# NVME.net
KiCad netlist of a schematic drawn in Altium Designer
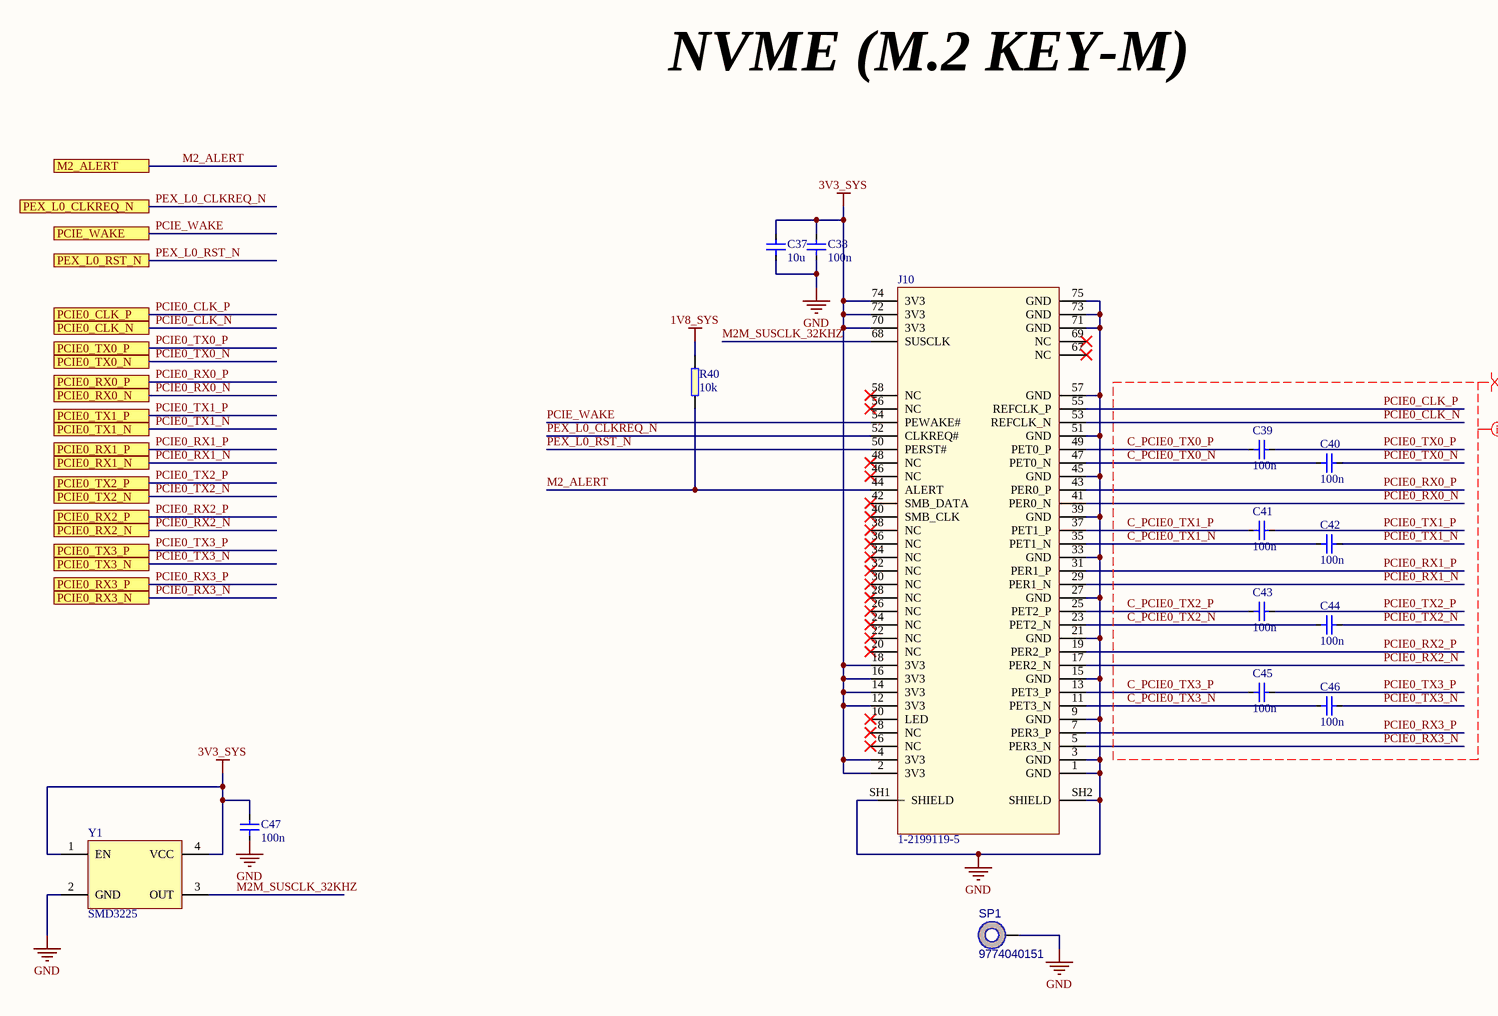
[diagram p0: NVME.SchDoc]

(export (version "E")
  (design (tool "Eeschema 10.0.6"))
  (components
    (comp (ref "C37")
      (value "10u")
      (footprint "C0402")
      (description "MLCC SMT Capacitor 10uF 0402")
      (fields (field (name "PARTNUMBER") "C_10u_0402") (field (name "MANUFACTURER") "TDK"))
      (libsource (lib "jetson-nano-baseboard") (part "C_10u_0402"))
    )
    (comp (ref "C38")
      (value "100n")
      (footprint "C0402")
      (description "MLCC SMT Capacitor 100n 0402")
      (fields (field (name "PARTNUMBER") "C_100n_0402") (field (name "MANUFACTURER") "TDK"))
      (libsource (lib "jetson-nano-baseboard") (part "C_100n_0402"))
    )
    (comp (ref "C39")
      (value "100n")
      (footprint "C0402")
      (description "MLCC SMT Capacitor 100n 0402")
      (fields (field (name "PARTNUMBER") "C_100n_0402") (field (name "MANUFACTURER") "TDK"))
      (libsource (lib "jetson-nano-baseboard") (part "C_100n_0402"))
    )
    (comp (ref "C40")
      (value "100n")
      (footprint "C0402")
      (description "MLCC SMT Capacitor 100n 0402")
      (fields (field (name "PARTNUMBER") "C_100n_0402") (field (name "MANUFACTURER") "TDK"))
      (libsource (lib "jetson-nano-baseboard") (part "C_100n_0402"))
    )
    (comp (ref "C41")
      (value "100n")
      (footprint "C0402")
      (description "MLCC SMT Capacitor 100n 0402")
      (fields (field (name "PARTNUMBER") "C_100n_0402") (field (name "MANUFACTURER") "TDK"))
      (libsource (lib "jetson-nano-baseboard") (part "C_100n_0402"))
    )
    (comp (ref "C42")
      (value "100n")
      (footprint "C0402")
      (description "MLCC SMT Capacitor 100n 0402")
      (fields (field (name "PARTNUMBER") "C_100n_0402") (field (name "MANUFACTURER") "TDK"))
      (libsource (lib "jetson-nano-baseboard") (part "C_100n_0402"))
    )
    (comp (ref "C43")
      (value "100n")
      (footprint "C0402")
      (description "MLCC SMT Capacitor 100n 0402")
      (fields (field (name "PARTNUMBER") "C_100n_0402") (field (name "MANUFACTURER") "TDK"))
      (libsource (lib "jetson-nano-baseboard") (part "C_100n_0402"))
    )
    (comp (ref "C44")
      (value "100n")
      (footprint "C0402")
      (description "MLCC SMT Capacitor 100n 0402")
      (fields (field (name "PARTNUMBER") "C_100n_0402") (field (name "MANUFACTURER") "TDK"))
      (libsource (lib "jetson-nano-baseboard") (part "C_100n_0402"))
    )
    (comp (ref "C45")
      (value "100n")
      (footprint "C0402")
      (description "MLCC SMT Capacitor 100n 0402")
      (fields (field (name "PARTNUMBER") "C_100n_0402") (field (name "MANUFACTURER") "TDK"))
      (libsource (lib "jetson-nano-baseboard") (part "C_100n_0402"))
    )
    (comp (ref "C46")
      (value "100n")
      (footprint "C0402")
      (description "MLCC SMT Capacitor 100n 0402")
      (fields (field (name "PARTNUMBER") "C_100n_0402") (field (name "MANUFACTURER") "TDK"))
      (libsource (lib "jetson-nano-baseboard") (part "C_100n_0402"))
    )
    (comp (ref "C47")
      (value "100n")
      (footprint "C0402")
      (description "MLCC SMT Capacitor 100n 0402")
      (fields (field (name "PARTNUMBER") "C_100n_0402") (field (name "MANUFACTURER") "TDK"))
      (libsource (lib "jetson-nano-baseboard") (part "C_100n_0402"))
    )
    (comp (ref "J10")
      (value "1-2199119-5")
      (footprint "1-2199119-5")
      (description "CONN FEMALE 67POS 0.020 GOLD")
      (fields (field (name "MANUFACTURER") "TE"))
      (libsource (lib "jetson-nano-baseboard") (part "1-2199119-5"))
    )
    (comp (ref "R40")
      (value "10k")
      (footprint "R0402")
      (description "RES, 10k, 0402")
      (fields (field (name "PARTNUMBER") "R_10k_0402") (field (name "MANUFACTURER") "MULTICOMP"))
      (libsource (lib "jetson-nano-baseboard") (part "R_10k_0402"))
    )
    (comp (ref "SP1")
      (value "9774040151")
      (footprint "MEC_STANDOFF_PTH_620C380P")
      (description "RND STANDOFF M2.5X0.45 STEEL 4MM")
      (fields (field (name "MANUFACTURER") "WURTH ELEKTRONIK"))
      (libsource (lib "jetson-nano-baseboard") (part "9774040151"))
    )
    (comp (ref "Y1")
      (value "SMD3225")
      (footprint "XTAL_SMD_4_032X025_D")
      (libsource (lib "jetson-nano-baseboard") (part "SMD3225"))
    )
  )
  (nets
    (net (code "1") (name "/C_PCIE0_TX0_N") (class "Default")
      (node (ref "C40") (pin "1") (pinfunction "1_1") (pintype "passive"))
      (node (ref "J10") (pin "47") (pinfunction "PET0_N_47") (pintype "passive"))
    )
    (net (code "2") (name "/C_PCIE0_TX0_P") (class "Default")
      (node (ref "C39") (pin "1") (pinfunction "1_1") (pintype "passive"))
      (node (ref "J10") (pin "49") (pinfunction "PET0_P_49") (pintype "passive"))
    )
    (net (code "3") (name "/C_PCIE0_TX1_N") (class "Default")
      (node (ref "C42") (pin "1") (pinfunction "1_1") (pintype "passive"))
      (node (ref "J10") (pin "35") (pinfunction "PET1_N_35") (pintype "passive"))
    )
    (net (code "4") (name "/C_PCIE0_TX1_P") (class "Default")
      (node (ref "C41") (pin "1") (pinfunction "1_1") (pintype "passive"))
      (node (ref "J10") (pin "37") (pinfunction "PET1_P_37") (pintype "passive"))
    )
    (net (code "5") (name "/C_PCIE0_TX2_N") (class "Default")
      (node (ref "C44") (pin "1") (pinfunction "1_1") (pintype "passive"))
      (node (ref "J10") (pin "23") (pinfunction "PET2_N_23") (pintype "passive"))
    )
    (net (code "6") (name "/C_PCIE0_TX2_P") (class "Default")
      (node (ref "C43") (pin "1") (pinfunction "1_1") (pintype "passive"))
      (node (ref "J10") (pin "25") (pinfunction "PET2_P_25") (pintype "passive"))
    )
    (net (code "7") (name "/C_PCIE0_TX3_N") (class "Default")
      (node (ref "C46") (pin "1") (pinfunction "1_1") (pintype "passive"))
      (node (ref "J10") (pin "11") (pinfunction "PET3_N_11") (pintype "passive"))
    )
    (net (code "8") (name "/C_PCIE0_TX3_P") (class "Default")
      (node (ref "C45") (pin "1") (pinfunction "1_1") (pintype "passive"))
      (node (ref "J10") (pin "13") (pinfunction "PET3_P_13") (pintype "passive"))
    )
    (net (code "9") (name "/M2M_SUSCLK_32KHZ") (class "Default")
      (node (ref "J10") (pin "68") (pinfunction "SUSCLK_68") (pintype "passive"))
      (node (ref "Y1") (pin "3") (pinfunction "OUT_3") (pintype "passive"))
    )
    (net (code "10") (name "/M2_ALERT") (class "Default")
      (node (ref "J10") (pin "44") (pinfunction "ALERT_44") (pintype "passive"))
      (node (ref "R40") (pin "1") (pintype "passive"))
    )
    (net (code "11") (name "/PCIE0_CLK_N") (class "Default")
      (node (ref "J10") (pin "53") (pinfunction "REFCLK_N_53") (pintype "passive"))
    )
    (net (code "12") (name "/PCIE0_CLK_P") (class "Default")
      (node (ref "J10") (pin "55") (pinfunction "REFCLK_P_55") (pintype "passive"))
    )
    (net (code "13") (name "/PCIE0_RX0_N") (class "Default")
      (node (ref "J10") (pin "41") (pinfunction "PER0_N_41") (pintype "passive"))
    )
    (net (code "14") (name "/PCIE0_RX0_P") (class "Default")
      (node (ref "J10") (pin "43") (pinfunction "PER0_P_43") (pintype "passive"))
    )
    (net (code "15") (name "/PCIE0_RX1_N") (class "Default")
      (node (ref "J10") (pin "29") (pinfunction "PER1_N_29") (pintype "passive"))
    )
    (net (code "16") (name "/PCIE0_RX1_P") (class "Default")
      (node (ref "J10") (pin "31") (pinfunction "PER1_P_31") (pintype "passive"))
    )
    (net (code "17") (name "/PCIE0_RX2_N") (class "Default")
      (node (ref "J10") (pin "17") (pinfunction "PER2_N_17") (pintype "passive"))
    )
    (net (code "18") (name "/PCIE0_RX2_P") (class "Default")
      (node (ref "J10") (pin "19") (pinfunction "PER2_P_19") (pintype "passive"))
    )
    (net (code "19") (name "/PCIE0_RX3_N") (class "Default")
      (node (ref "J10") (pin "5") (pinfunction "PER3_N_5") (pintype "passive"))
    )
    (net (code "20") (name "/PCIE0_RX3_P") (class "Default")
      (node (ref "J10") (pin "7") (pinfunction "PER3_P_7") (pintype "passive"))
    )
    (net (code "21") (name "/PCIE0_TX0_N") (class "Default")
      (node (ref "C40") (pin "2") (pinfunction "2_2") (pintype "passive"))
    )
    (net (code "22") (name "/PCIE0_TX0_P") (class "Default")
      (node (ref "C39") (pin "2") (pinfunction "2_2") (pintype "passive"))
    )
    (net (code "23") (name "/PCIE0_TX1_N") (class "Default")
      (node (ref "C42") (pin "2") (pinfunction "2_2") (pintype "passive"))
    )
    (net (code "24") (name "/PCIE0_TX1_P") (class "Default")
      (node (ref "C41") (pin "2") (pinfunction "2_2") (pintype "passive"))
    )
    (net (code "25") (name "/PCIE0_TX2_N") (class "Default")
      (node (ref "C44") (pin "2") (pinfunction "2_2") (pintype "passive"))
    )
    (net (code "26") (name "/PCIE0_TX2_P") (class "Default")
      (node (ref "C43") (pin "2") (pinfunction "2_2") (pintype "passive"))
    )
    (net (code "27") (name "/PCIE0_TX3_N") (class "Default")
      (node (ref "C46") (pin "2") (pinfunction "2_2") (pintype "passive"))
    )
    (net (code "28") (name "/PCIE0_TX3_P") (class "Default")
      (node (ref "C45") (pin "2") (pinfunction "2_2") (pintype "passive"))
    )
    (net (code "29") (name "/PCIE_WAKE") (class "Default")
      (node (ref "J10") (pin "54") (pinfunction "PEWAKE#_54") (pintype "passive"))
    )
    (net (code "30") (name "/PEX_L0_CLKREQ_N") (class "Default")
      (node (ref "J10") (pin "52") (pinfunction "CLKREQ#_52") (pintype "passive"))
    )
    (net (code "31") (name "/PEX_L0_RST_N") (class "Default")
      (node (ref "J10") (pin "50") (pinfunction "PERST#_50") (pintype "passive"))
    )
    (net (code "32") (name "1V8_SYS") (class "Default") (node (ref "R40") (pin "2") (pintype "passive")))
    (net (code "33") (name "3V3_SYS") (class "Default")
      (node (ref "C37") (pin "2") (pinfunction "2_2") (pintype "passive"))
      (node (ref "C38") (pin "2") (pinfunction "2_2") (pintype "passive"))
      (node (ref "C47") (pin "2") (pinfunction "2_2") (pintype "passive"))
      (node (ref "J10") (pin "12") (pinfunction "3V3_12") (pintype "passive"))
      (node (ref "J10") (pin "14") (pinfunction "3V3_14") (pintype "passive"))
      (node (ref "J10") (pin "16") (pinfunction "3V3_16") (pintype "passive"))
      (node (ref "J10") (pin "18") (pinfunction "3V3_18") (pintype "passive"))
      (node (ref "J10") (pin "2") (pinfunction "3V3_2") (pintype "passive"))
      (node (ref "J10") (pin "4") (pinfunction "3V3_4") (pintype "passive"))
      (node (ref "J10") (pin "70") (pinfunction "3V3_70") (pintype "passive"))
      (node (ref "J10") (pin "72") (pinfunction "3V3_72") (pintype "passive"))
      (node (ref "J10") (pin "74") (pinfunction "3V3_74") (pintype "passive"))
      (node (ref "Y1") (pin "1") (pinfunction "EN_1") (pintype "passive"))
      (node (ref "Y1") (pin "4") (pinfunction "VCC_4") (pintype "passive"))
    )
    (net (code "34") (name "GND") (class "Default")
      (node (ref "C37") (pin "1") (pinfunction "1_1") (pintype "passive"))
      (node (ref "C38") (pin "1") (pinfunction "1_1") (pintype "passive"))
      (node (ref "C47") (pin "1") (pinfunction "1_1") (pintype "passive"))
      (node (ref "J10") (pin "1") (pinfunction "GND_1") (pintype "passive"))
      (node (ref "J10") (pin "15") (pinfunction "GND_15") (pintype "passive"))
      (node (ref "J10") (pin "21") (pinfunction "GND_21") (pintype "passive"))
      (node (ref "J10") (pin "27") (pinfunction "GND_27") (pintype "passive"))
      (node (ref "J10") (pin "3") (pinfunction "GND_3") (pintype "passive"))
      (node (ref "J10") (pin "33") (pinfunction "GND_33") (pintype "passive"))
      (node (ref "J10") (pin "39") (pinfunction "GND_39") (pintype "passive"))
      (node (ref "J10") (pin "45") (pinfunction "GND_45") (pintype "passive"))
      (node (ref "J10") (pin "51") (pinfunction "GND_51") (pintype "passive"))
      (node (ref "J10") (pin "57") (pinfunction "GND_57") (pintype "passive"))
      (node (ref "J10") (pin "71") (pinfunction "GND_71") (pintype "passive"))
      (node (ref "J10") (pin "73") (pinfunction "GND_73") (pintype "passive"))
      (node (ref "J10") (pin "75") (pinfunction "GND_75") (pintype "passive"))
      (node (ref "J10") (pin "9") (pinfunction "GND_9") (pintype "passive"))
      (node (ref "J10") (pin "SH1") (pinfunction "SHIELD_SH1") (pintype "passive"))
      (node (ref "J10") (pin "SH2") (pinfunction "SHIELD_SH2") (pintype "passive"))
      (node (ref "SP1") (pin "1") (pinfunction "1_1") (pintype "passive"))
      (node (ref "Y1") (pin "2") (pinfunction "GND_2") (pintype "passive"))
    )
    (net (code "35") (name "unconnected-(J10-LED-Pad10)") (class "Default")
      (node (ref "J10") (pin "10") (pinfunction "LED_10") (pintype "passive+no_connect"))
    )
    (net (code "36") (name "unconnected-(J10-NC-Pad6)") (class "Default")
      (node (ref "J10") (pin "6") (pinfunction "NC_6") (pintype "passive+no_connect"))
    )
    (net (code "37") (name "unconnected-(J10-NC-Pad8)") (class "Default")
      (node (ref "J10") (pin "8") (pinfunction "NC_8") (pintype "passive+no_connect"))
    )
    (net (code "38") (name "unconnected-(J10-NC-Pad20)") (class "Default")
      (node (ref "J10") (pin "20") (pinfunction "NC_20") (pintype "passive+no_connect"))
    )
    (net (code "39") (name "unconnected-(J10-NC-Pad22)") (class "Default")
      (node (ref "J10") (pin "22") (pinfunction "NC_22") (pintype "passive+no_connect"))
    )
    (net (code "40") (name "unconnected-(J10-NC-Pad24)") (class "Default")
      (node (ref "J10") (pin "24") (pinfunction "NC_24") (pintype "passive+no_connect"))
    )
    (net (code "41") (name "unconnected-(J10-NC-Pad26)") (class "Default")
      (node (ref "J10") (pin "26") (pinfunction "NC_26") (pintype "passive+no_connect"))
    )
    (net (code "42") (name "unconnected-(J10-NC-Pad28)") (class "Default")
      (node (ref "J10") (pin "28") (pinfunction "NC_28") (pintype "passive+no_connect"))
    )
    (net (code "43") (name "unconnected-(J10-NC-Pad30)") (class "Default")
      (node (ref "J10") (pin "30") (pinfunction "NC_30") (pintype "passive+no_connect"))
    )
    (net (code "44") (name "unconnected-(J10-NC-Pad32)") (class "Default")
      (node (ref "J10") (pin "32") (pinfunction "NC_32") (pintype "passive+no_connect"))
    )
    (net (code "45") (name "unconnected-(J10-NC-Pad34)") (class "Default")
      (node (ref "J10") (pin "34") (pinfunction "NC_34") (pintype "passive+no_connect"))
    )
    (net (code "46") (name "unconnected-(J10-NC-Pad36)") (class "Default")
      (node (ref "J10") (pin "36") (pinfunction "NC_36") (pintype "passive+no_connect"))
    )
    (net (code "47") (name "unconnected-(J10-NC-Pad38)") (class "Default")
      (node (ref "J10") (pin "38") (pinfunction "NC_38") (pintype "passive+no_connect"))
    )
    (net (code "48") (name "unconnected-(J10-NC-Pad46)") (class "Default")
      (node (ref "J10") (pin "46") (pinfunction "NC_46") (pintype "passive+no_connect"))
    )
    (net (code "49") (name "unconnected-(J10-NC-Pad48)") (class "Default")
      (node (ref "J10") (pin "48") (pinfunction "NC_48") (pintype "passive+no_connect"))
    )
    (net (code "50") (name "unconnected-(J10-NC-Pad56)") (class "Default")
      (node (ref "J10") (pin "56") (pinfunction "NC_56") (pintype "passive+no_connect"))
    )
    (net (code "51") (name "unconnected-(J10-NC-Pad58)") (class "Default")
      (node (ref "J10") (pin "58") (pinfunction "NC_58") (pintype "passive+no_connect"))
    )
    (net (code "52") (name "unconnected-(J10-NC-Pad67)") (class "Default")
      (node (ref "J10") (pin "67") (pinfunction "NC_67") (pintype "passive+no_connect"))
    )
    (net (code "53") (name "unconnected-(J10-NC-Pad69)") (class "Default")
      (node (ref "J10") (pin "69") (pinfunction "NC_69") (pintype "passive+no_connect"))
    )
    (net (code "54") (name "unconnected-(J10-SMB_CLK-Pad40)") (class "Default")
      (node (ref "J10") (pin "40") (pinfunction "SMB_CLK_40") (pintype "passive+no_connect"))
    )
    (net (code "55") (name "unconnected-(J10-SMB_DATA-Pad42)") (class "Default")
      (node (ref "J10") (pin "42") (pinfunction "SMB_DATA_42") (pintype "passive+no_connect"))
    )
  )
)
